# Power_Managment.net
KiCad netlist of a schematic drawn in Altium Designer
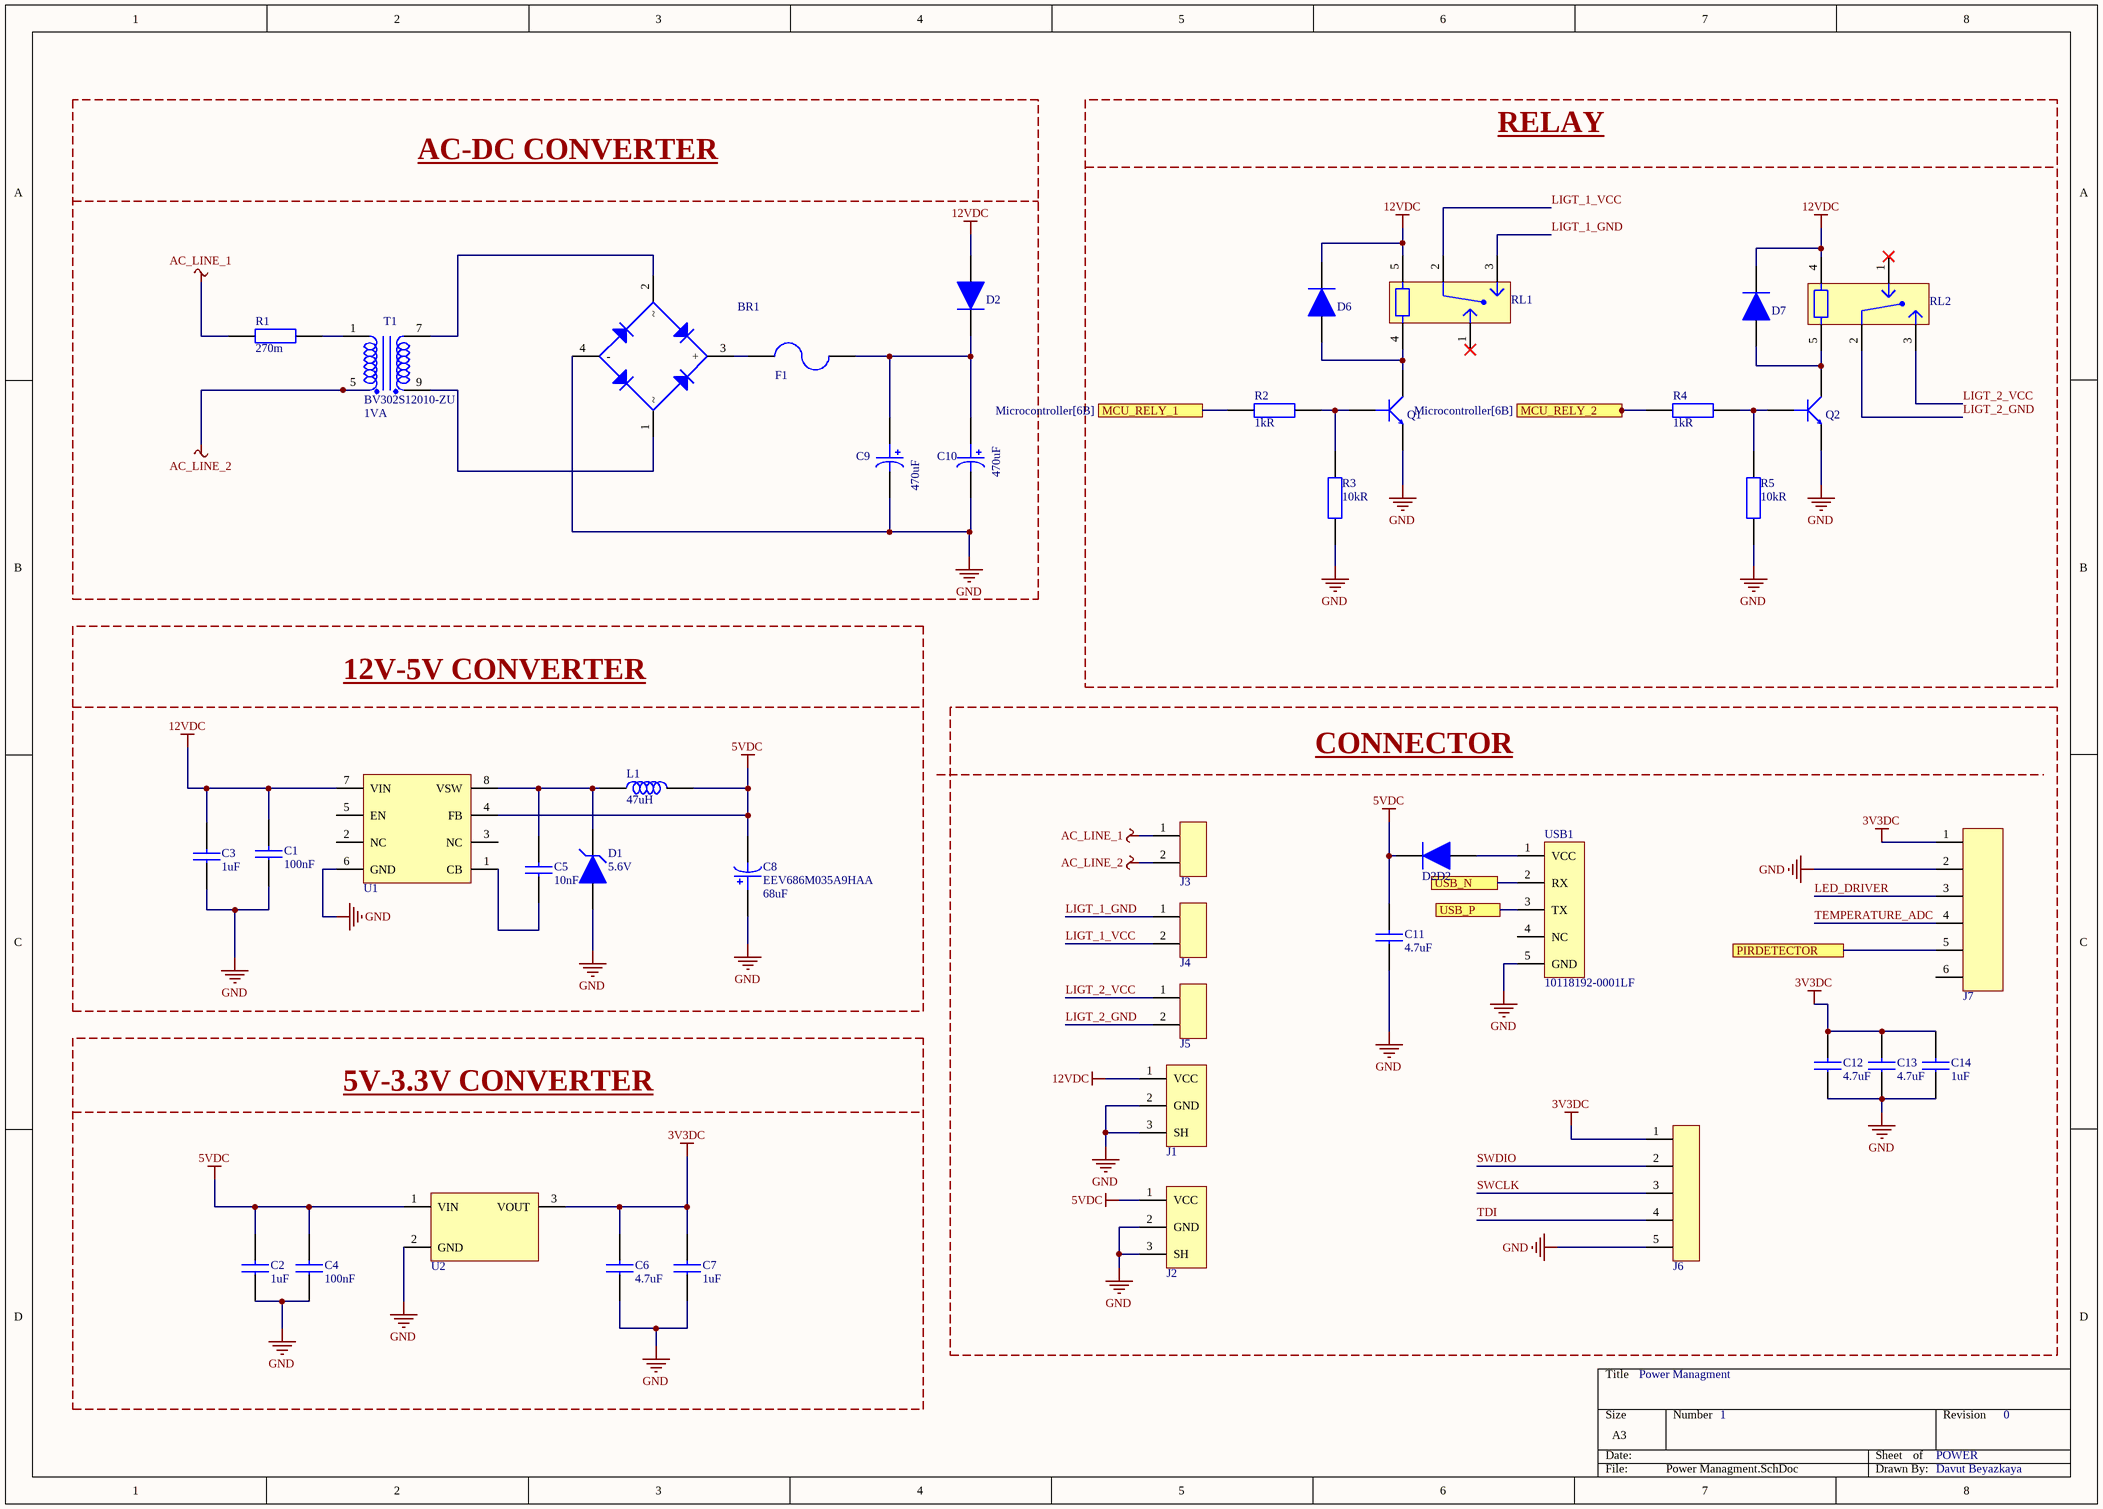
[diagram p0: Power Managment.SchDoc]

(export (version "E")
  (design (tool "Eeschema 10.0.6"))
  (components
    (comp (ref "BR1")
      (value "DB105STR")
      (footprint "DB105STR")
      (description "Bridge Diode AC-DC")
      (fields (field (name "MANUFACTURER") "Sangdest Microelectronics") (field (name "DESIGNED BY") "BERK"))
      (libsource (lib "UDEMY_Library") (part "DB105STR"))
    )
    (comp (ref "C1")
      (value "CL21B104KBCNNNC")
      (footprint "CAP_0805")
      (description "CAP CER 100nF %10 0805")
      (fields
        (field (name "MANUFACTURER") "Samsung")
        (field (name "TOLERANCE") "10%")
        (field (name "CAPACITANCE") "100nF")
        (field (name "DESIGNED BY") "BERK")
      )
      (libsource (lib "UDEMY_Library") (part "CAP CER 100nF 0805"))
    )
    (comp (ref "C2")
      (value "CL21B105KBFNNNE")
      (footprint "CAP_0805")
      (description "CAP CER 1uF %10 0805")
      (fields
        (field (name "MANUFACTURER") "Samsung")
        (field (name "TOLERANCE") "10%")
        (field (name "CAPACITANCE") "1uF")
        (field (name "DESIGNED BY") "BERK")
      )
      (libsource (lib "UDEMY_Library") (part "CAP CER 1uF 0805"))
    )
    (comp (ref "C3")
      (value "CL21B105KBFNNNE")
      (footprint "CAP_0805")
      (description "CAP CER 1uF %10 0805")
      (fields
        (field (name "MANUFACTURER") "Samsung")
        (field (name "TOLERANCE") "10%")
        (field (name "CAPACITANCE") "1uF")
        (field (name "DESIGNED BY") "BERK")
      )
      (libsource (lib "UDEMY_Library") (part "CAP CER 1uF 0805"))
    )
    (comp (ref "C4")
      (value "C0603C104K5RACTU")
      (footprint "CAP_0603")
      (description "CAP CER 100nF %10 0603 SMD")
      (fields
        (field (name "MANUFACTURER") "KEMET")
        (field (name "TOLERANCE") "10%")
        (field (name "CAPACITANCE") "100nF")
        (field (name "DESIGNED BY") "BERK")
      )
      (libsource (lib "UDEMY_Library") (part "CAP CER 100nF 0603"))
    )
    (comp (ref "C5")
      (value "0603B103K160CT")
      (footprint "CAP_0603")
      (description "CAP CER 10nF %10 0603")
      (fields
        (field (name "MANUFACTURER") "Walsin Technologies")
        (field (name "TOLERANCE") "10%")
        (field (name "CAPACITANCE") "10nF")
        (field (name "DESIGNED BY") "BERK")
      )
      (libsource (lib "UDEMY_Library") (part "CAP CER 10nF 0603"))
    )
    (comp (ref "C6")
      (value "CL21A475KAQNNNE")
      (footprint "CAP_0805")
      (description "CAP CER 4.7uF %10 0805")
      (fields
        (field (name "MANUFACTURER") "Samsung")
        (field (name "TOLERANCE") "10%")
        (field (name "CAPACITANCE") "4.7uF")
        (field (name "DESIGNED BY") "BERK")
      )
      (libsource (lib "UDEMY_Library") (part "CAP CER 4.7uF 0805"))
    )
    (comp (ref "C7")
      (value "CL21B105KBFNNNE")
      (footprint "CAP_0805")
      (description "CAP CER 1uF %10 0805")
      (fields
        (field (name "MANUFACTURER") "Samsung")
        (field (name "TOLERANCE") "10%")
        (field (name "CAPACITANCE") "1uF")
        (field (name "DESIGNED BY") "BERK")
      )
      (libsource (lib "UDEMY_Library") (part "CAP CER 1uF 0805"))
    )
    (comp (ref "C8")
      (value "EEV686M035A9HAA")
      (footprint "CAP_EEVseries")
      (description "Cap Aluminum Lytic 68uF 35V 20% (6.3 X 7.7mm) SMD 280mA 2000h 105C T/R")
      (fields
        (field (name "MANUFACTURER") "KEMET")
        (field (name "TOLERANCE") "20%")
        (field (name "CAPACITANCE") "68uF")
      )
      (libsource (lib "UDEMY_Library") (part "CAP ALU 68uF"))
    )
    (comp (ref "C9")
      (value "ESH477M050AH4AA")
      (footprint "CAP_RADIAL_D10_P5")
      (description "CAP ALU ELEC 470uF 50V RADIAL")
      (fields
        (field (name "MANUFACTURER") "KEMET")
        (field (name "TOLERANCE") "20%")
        (field (name "CAPACITANCE") "470uF")
        (field (name "DESIGNED BY") "BERK")
      )
      (libsource (lib "UDEMY_Library") (part "CAP ALU ELEC 470uF 50V"))
    )
    (comp (ref "C10")
      (value "ESH477M050AH4AA")
      (footprint "CAP_RADIAL_D10_P5")
      (description "CAP ALU ELEC 470uF 50V RADIAL")
      (fields
        (field (name "MANUFACTURER") "KEMET")
        (field (name "TOLERANCE") "20%")
        (field (name "CAPACITANCE") "470uF")
        (field (name "DESIGNED BY") "BERK")
      )
      (libsource (lib "UDEMY_Library") (part "CAP ALU ELEC 470uF 50V"))
    )
    (comp (ref "C11")
      (value "CL21A475KAQNNNE")
      (footprint "CAP_0805")
      (description "CAP CER 4.7uF %10 0805")
      (fields
        (field (name "MANUFACTURER") "Samsung")
        (field (name "TOLERANCE") "10%")
        (field (name "CAPACITANCE") "4.7uF")
        (field (name "DESIGNED BY") "BERK")
      )
      (libsource (lib "UDEMY_Library") (part "CAP CER 4.7uF 0805"))
    )
    (comp (ref "C12")
      (value "CL21A475KAQNNNE")
      (footprint "CAP_0805")
      (description "CAP CER 4.7uF %10 0805")
      (fields
        (field (name "MANUFACTURER") "Samsung")
        (field (name "TOLERANCE") "10%")
        (field (name "CAPACITANCE") "4.7uF")
        (field (name "DESIGNED BY") "BERK")
      )
      (libsource (lib "UDEMY_Library") (part "CAP CER 4.7uF 0805"))
    )
    (comp (ref "C13")
      (value "CL21A475KAQNNNE")
      (footprint "CAP_0805")
      (description "CAP CER 4.7uF %10 0805")
      (fields
        (field (name "MANUFACTURER") "Samsung")
        (field (name "TOLERANCE") "10%")
        (field (name "CAPACITANCE") "4.7uF")
        (field (name "DESIGNED BY") "BERK")
      )
      (libsource (lib "UDEMY_Library") (part "CAP CER 4.7uF 0805"))
    )
    (comp (ref "C14")
      (value "CL21B105KBFNNNE")
      (footprint "CAP_0805")
      (description "CAP CER 1uF %10 0805")
      (fields
        (field (name "MANUFACTURER") "Samsung")
        (field (name "TOLERANCE") "10%")
        (field (name "CAPACITANCE") "1uF")
        (field (name "DESIGNED BY") "BERK")
      )
      (libsource (lib "UDEMY_Library") (part "CAP CER 1uF 0805"))
    )
    (comp (ref "D1")
      (value "1SMB5919BT3G")
      (footprint "SMB")
      (description "Diode Zener Single 5.6V 5% 3W 2-Pin SMB T/R")
      (fields
        (field (name "MANUFACTURER") "ON Semiconductor")
        (field (name "TOLERANCE") "5%")
        (field (name "WORKING VOLTAGE") "5.6V")
        (field (name "DESIGNED BY") "BERK")
      )
      (libsource (lib "UDEMY_Library") (part "1SMB5919BT3G"))
    )
    (comp (ref "D2")
      (value "1N4148WS")
      (footprint "SOD323F")
      (description "Diode, Single, 75 V, 150 mA, 1 V, 4 ns")
      (fields
        (field (name "MANUFACTURER") "ON Semiconductor / Fairchild")
        (field (name "DESIGNED BY") "BERK")
      )
      (libsource (lib "UDEMY_Library") (part "1N4148WS"))
    )
    (comp (ref "D2D2")
      (value "1N4148WS")
      (footprint "SOD323F")
      (description "Diode, Single, 75 V, 150 mA, 1 V, 4 ns")
      (fields
        (field (name "MANUFACTURER") "ON Semiconductor / Fairchild")
        (field (name "DESIGNED BY") "BERK")
      )
      (libsource (lib "UDEMY_Library") (part "1N4148WS"))
    )
    (comp (ref "D6")
      (value "1N4148WS")
      (footprint "SOD323F")
      (description "Diode, Single, 75 V, 150 mA, 1 V, 4 ns")
      (fields
        (field (name "MANUFACTURER") "ON Semiconductor / Fairchild")
        (field (name "DESIGNED BY") "BERK")
      )
      (libsource (lib "UDEMY_Library") (part "1N4148WS"))
    )
    (comp (ref "D7")
      (value "1N4148WS")
      (footprint "SOD323F")
      (description "Diode, Single, 75 V, 150 mA, 1 V, 4 ns")
      (fields
        (field (name "MANUFACTURER") "ON Semiconductor / Fairchild")
        (field (name "DESIGNED BY") "BERK")
      )
      (libsource (lib "UDEMY_Library") (part "1N4148WS"))
    )
    (comp (ref "F1")
      (value "3413.0216.22")
      (footprint "3413.0216.22")
      (description "FUSE BRD MNT 1A 32VAC 63VDC 1206")
      (fields (field (name "MANUFACTURER") "Schurter") (field (name "DESIGNED BY") "BERK"))
      (libsource (lib "UDEMY_Library") (part "FUSE 3413.0216.22"))
    )
    (comp (ref "J1")
      (value "PJ-037AH-SMT-TR")
      (footprint "JACK")
      (description "DC Power Connectors Power Jacks")
      (fields (field (name "MANUFACTURER") "CUI") (field (name "DESIGNED BY") "BERK"))
      (libsource (lib "UDEMY_Library") (part "PJ-037AH-SMT-TR"))
    )
    (comp (ref "J2")
      (value "PJ-037AH-SMT-TR")
      (footprint "JACK")
      (description "DC Power Connectors Power Jacks")
      (fields (field (name "MANUFACTURER") "CUI") (field (name "DESIGNED BY") "BERK"))
      (libsource (lib "UDEMY_Library") (part "PJ-037AH-SMT-TR"))
    )
    (comp (ref "J3")
      (value "TBP01R1-508-02BE")
      (footprint "TBP01R1-508")
      (description "Conn Shrouded Header HDR 2 POS 5.08mm Solder RA Side Entry Thru-Hole Bag")
      (fields (field (name "MANUFACTURER") "CUI") (field (name "DESIGNED BY") "BERK"))
      (libsource (lib "UDEMY_Library") (part "TBP01R1-508-02BE"))
    )
    (comp (ref "J4")
      (value "TBP01R1-508-02BE")
      (footprint "TBP01R1-508")
      (description "Conn Shrouded Header HDR 2 POS 5.08mm Solder RA Side Entry Thru-Hole Bag")
      (fields (field (name "MANUFACTURER") "CUI") (field (name "DESIGNED BY") "BERK"))
      (libsource (lib "UDEMY_Library") (part "TBP01R1-508-02BE"))
    )
    (comp (ref "J5")
      (value "TBP01R1-508-02BE")
      (footprint "TBP01R1-508")
      (description "Conn Shrouded Header HDR 2 POS 5.08mm Solder RA Side Entry Thru-Hole Bag")
      (fields (field (name "MANUFACTURER") "CUI") (field (name "DESIGNED BY") "BERK"))
      (libsource (lib "UDEMY_Library") (part "TBP01R1-508-02BE"))
    )
    (comp (ref "J6")
      (value "SMH-105-02-L-S")
      (footprint "PINHEADER1X5_RA")
      (description ".100 C.L. HORIZONTAL SMT SOCKET")
      (fields (field (name "MANUFACTURER") "Samtec") (field (name "DESIGNED BY") "BERK"))
      (libsource (lib "UDEMY_Library") (part "SMH-105-02-L-S"))
    )
    (comp (ref "J7")
      (value "64800611622")
      (footprint "64800611622")
      (description "1.50mm 6PIN Connector")
      (fields (field (name "MANUFACTURER") "Wurth Electronics"))
      (libsource (lib "UDEMY_Library") (part "64800611622_conn_6pin"))
    )
    (comp (ref "L1")
      (value "78438335470")
      (footprint "IND_1212")
      (description "FIXED IND 47UH 390MA 2.3 OHM SMD")
      (fields
        (field (name "MANUFACTURER") "Wurth Electronics")
        (field (name "TOLERANCE") "30%")
        (field (name "INDUCTANCE") "47uH")
        (field (name "DESIGNED BY") "BERK")
      )
      (libsource (lib "UDEMY_Library") (part "IND 47uH"))
    )
    (comp (ref "Q1")
      (value "MMBT3904-7-F")
      (footprint "SOT-23F")
      (description "Transistor General Purpose BJT NPN 40 Volt 0.2A Automotive 3-Pin SOT-23")
      (fields (field (name "MANUFACTURER") "Diodes Zetex") (field (name "DESIGNED BY") "BERK"))
      (libsource (lib "UDEMY_Library") (part "MMBT3904-7-F"))
    )
    (comp (ref "Q2")
      (value "MMBT3904-7-F")
      (footprint "SOT-23F")
      (description "Transistor General Purpose BJT NPN 40 Volt 0.2A Automotive 3-Pin SOT-23")
      (fields (field (name "MANUFACTURER") "Diodes Zetex") (field (name "DESIGNED BY") "BERK"))
      (libsource (lib "UDEMY_Library") (part "MMBT3904-7-F"))
    )
    (comp (ref "R1")
      (value "5WD27")
      (footprint "RES_AXIAL_W")
      (description "Resistor 5 Watt Cermet Wirewound Flameproof .27 Ohm 5% Axial Lead")
      (fields
        (field (name "MANUFACTURER") "NTE Electronics")
        (field (name "TOLERANCE") "5%")
        (field (name "RESISTANCE") "270m")
        (field (name "DESIGNED BY") "BERK")
      )
      (libsource (lib "UDEMY_Library") (part "5WD27"))
    )
    (comp (ref "R2")
      (value "RC0603FR-0710KL")
      (footprint "RES_0603")
      (description "RES 1K %1 OHM 0603 SMD")
      (fields
        (field (name "MANUFACTURER") "Yageo")
        (field (name "MANUFACTURER PART NUMBER") "RC0603JR-071KL")
        (field (name "RESISTANCE") "1kR")
        (field (name "DESIGNED BY") "BERK")
      )
      (libsource (lib "UDEMY_Library") (part "RES 1K OHM 0603"))
    )
    (comp (ref "R3")
      (value "RC0603FR-0710KL")
      (footprint "RES_0603")
      (description "RES 10K %1 OHM 0603 SMD")
      (fields
        (field (name "MANUFACTURER") "Yageo")
        (field (name "TOLERANCE") "1%")
        (field (name "RESISTANCE") "10kR")
        (field (name "DESIGNED BY") "BERK")
      )
      (libsource (lib "UDEMY_Library") (part "RES 10K OHM 0603"))
    )
    (comp (ref "R4")
      (value "RC0603FR-0710KL")
      (footprint "RES_0603")
      (description "RES 1K %1 OHM 0603 SMD")
      (fields
        (field (name "MANUFACTURER") "Yageo")
        (field (name "MANUFACTURER PART NUMBER") "RC0603JR-071KL")
        (field (name "RESISTANCE") "1kR")
        (field (name "DESIGNED BY") "BERK")
      )
      (libsource (lib "UDEMY_Library") (part "RES 1K OHM 0603"))
    )
    (comp (ref "R5")
      (value "RC0603FR-0710KL")
      (footprint "RES_0603")
      (description "RES 10K %1 OHM 0603 SMD")
      (fields
        (field (name "MANUFACTURER") "Yageo")
        (field (name "TOLERANCE") "1%")
        (field (name "RESISTANCE") "10kR")
        (field (name "DESIGNED BY") "BERK")
      )
      (libsource (lib "UDEMY_Library") (part "RES 10K OHM 0603"))
    )
    (comp (ref "RL1")
      (value "ALQ112")
      (footprint "ALQ112")
      (description "General Purpose Relay SPDT (1 Form C) 12VDC Coil Through Hole")
      (fields (field (name "MANUFACTURER") "Panasonic") (field (name "DESIGNED BY") "BERK"))
      (libsource (lib "UDEMY_Library") (part "ALQ112"))
    )
    (comp (ref "RL2")
      (value "ALQ112")
      (footprint "ALQ112")
      (description "General Purpose Relay SPDT (1 Form C) 12VDC Coil Through Hole")
      (fields (field (name "MANUFACTURER") "Panasonic") (field (name "DESIGNED BY") "BERK"))
      (libsource (lib "") (part "ALQ112_1"))
    )
    (comp (ref "T1")
      (value "BV302S12010-ZU")
      (footprint "BV302S")
      (description "230-12 Transformer 1VA")
      (fields
        (field (name "MANUFACTURER") "Zettler Magnetics")
        (field (name "RATED POWER") "1VA")
        (field (name "DESIGNED BY") "BERK")
      )
      (libsource (lib "UDEMY_Library") (part "BV302S12010-ZU"))
    )
    (comp (ref "U1")
      (value "LM2675MX-12/NOPB")
      (footprint "SOIC8")
      (description "Switching Voltage Regulators Pwr Cnvtr Hi Eff 1A SD Vtg Reg")
      (fields (field (name "MANUFACTURER") "TI National Semiconductor") (field (name "DESIGNED BY") "BERK"))
      (libsource (lib "UDEMY_Library") (part "LM2675MX-12/NOPB"))
    )
    (comp (ref "U2")
      (value "AP7361-33E-13")
      (footprint "SOT223")
      (description "LDO Regulator Pos 3.3V 1A 4-Pin(3+Tab) SOT-223 T/R")
      (fields (field (name "MANUFACTURER") "Diodes") (field (name "DESIGNED BY") "BERK"))
      (libsource (lib "UDEMY_Library") (part "AP7361-33E-13"))
    )
    (comp (ref "USB1")
      (value "10118192-0001LF")
      (footprint "MICRO_B_USB")
      (description "CONN RCPT USB2.0 MICRO B SMD R/A")
      (fields (field (name "MANUFACTURER") "Amphenol FCI") (field (name "DESIGNED BY") "BERK"))
      (libsource (lib "UDEMY_Library") (part "Micro B USB Connector"))
    )
  )
  (nets
    (net (code "1") (name "/LED_DRIVER") (class "Default") (node (ref "J7") (pin "3") (pintype "power_in")))
    (net (code "2") (name "/LIGT_1_GND") (class "Default")
      (node (ref "J4") (pin "1") (pinfunction "1_1") (pintype "power_in"))
      (node (ref "RL1") (pin "3") (pinfunction "3_3") (pintype "passive"))
    )
    (net (code "3") (name "/LIGT_1_VCC") (class "Default")
      (node (ref "J4") (pin "2") (pinfunction "2_2") (pintype "power_in"))
      (node (ref "RL1") (pin "2") (pinfunction "2_2") (pintype "passive"))
    )
    (net (code "4") (name "/LIGT_2_GND") (class "Default")
      (node (ref "J5") (pin "2") (pinfunction "2_2") (pintype "power_in"))
      (node (ref "RL2") (pin "2") (pinfunction "2_2") (pintype "passive"))
    )
    (net (code "5") (name "/LIGT_2_VCC") (class "Default")
      (node (ref "J5") (pin "1") (pinfunction "1_1") (pintype "power_in"))
      (node (ref "RL2") (pin "3") (pinfunction "3_3") (pintype "passive"))
    )
    (net (code "6") (name "/MCU_RELY_1") (class "Default")
      (node (ref "R2") (pin "1") (pinfunction "1_1") (pintype "passive"))
    )
    (net (code "7") (name "/MCU_RELY_2") (class "Default")
      (node (ref "R4") (pin "1") (pinfunction "1_1") (pintype "passive"))
    )
    (net (code "8") (name "/PIRDETECTOR") (class "Default") (node (ref "J7") (pin "5") (pintype "power_in")))
    (net (code "9") (name "/SWCLK") (class "Default")
      (node (ref "J6") (pin "3") (pinfunction "3_3") (pintype "power_in"))
    )
    (net (code "10") (name "/SWDIO") (class "Default")
      (node (ref "J6") (pin "2") (pinfunction "2_2") (pintype "power_in"))
    )
    (net (code "11") (name "/TDI") (class "Default")
      (node (ref "J6") (pin "4") (pinfunction "4_4") (pintype "power_in"))
    )
    (net (code "12") (name "/TEMPERATURE_ADC") (class "Default")
      (node (ref "J7") (pin "4") (pintype "power_in"))
    )
    (net (code "13") (name "/USB_N") (class "Default")
      (node (ref "USB1") (pin "2") (pinfunction "RX_2") (pintype "power_in"))
    )
    (net (code "14") (name "/USB_P") (class "Default")
      (node (ref "USB1") (pin "3") (pinfunction "TX_3") (pintype "power_in"))
    )
    (net (code "15") (name "3V3DC") (class "Default")
      (node (ref "C12") (pin "2") (pinfunction "2_2") (pintype "passive"))
      (node (ref "C13") (pin "2") (pinfunction "2_2") (pintype "passive"))
      (node (ref "C14") (pin "2") (pinfunction "2_2") (pintype "passive"))
      (node (ref "C6") (pin "2") (pinfunction "2_2") (pintype "passive"))
      (node (ref "C7") (pin "2") (pinfunction "2_2") (pintype "passive"))
      (node (ref "J6") (pin "1") (pinfunction "1_1") (pintype "power_in"))
      (node (ref "J7") (pin "1") (pintype "power_in"))
      (node (ref "U2") (pin "3") (pinfunction "VOUT_3") (pintype "passive"))
    )
    (net (code "16") (name "5VDC") (class "Default")
      (node (ref "C11") (pin "2") (pinfunction "2_2") (pintype "passive"))
      (node (ref "C2") (pin "2") (pinfunction "2_2") (pintype "passive"))
      (node (ref "C4") (pin "2") (pinfunction "2_2") (pintype "passive"))
      (node (ref "C8") (pin "2") (pinfunction "2_2") (pintype "passive"))
      (node (ref "D2D2") (pin "1") (pinfunction "1_1") (pintype "power_in"))
      (node (ref "J2") (pin "1") (pinfunction "VCC_1") (pintype "power_in"))
      (node (ref "L1") (pin "2") (pinfunction "2_2") (pintype "passive"))
      (node (ref "U1") (pin "4") (pinfunction "FB_4") (pintype "passive"))
      (node (ref "U2") (pin "1") (pinfunction "VIN_1") (pintype "passive"))
    )
    (net (code "17") (name "12VDC") (class "Default")
      (node (ref "C1") (pin "2") (pinfunction "2_2") (pintype "passive"))
      (node (ref "C3") (pin "2") (pinfunction "2_2") (pintype "passive"))
      (node (ref "D2") (pin "2") (pinfunction "2_2") (pintype "power_in"))
      (node (ref "D6") (pin "1") (pinfunction "1_1") (pintype "power_in"))
      (node (ref "D7") (pin "1") (pinfunction "1_1") (pintype "power_in"))
      (node (ref "J1") (pin "1") (pinfunction "VCC_1") (pintype "power_in"))
      (node (ref "RL1") (pin "5") (pinfunction "5_5") (pintype "passive"))
      (node (ref "RL2") (pin "4") (pinfunction "4_4") (pintype "passive"))
      (node (ref "U1") (pin "7") (pinfunction "VIN_7") (pintype "passive"))
    )
    (net (code "18") (name "AC_LINE_1") (class "Default")
      (node (ref "J3") (pin "1") (pinfunction "1_1") (pintype "power_in"))
      (node (ref "R1") (pin "1") (pinfunction "1_1") (pintype "passive"))
    )
    (net (code "19") (name "AC_LINE_2") (class "Default")
      (node (ref "J3") (pin "2") (pinfunction "2_2") (pintype "power_in"))
      (node (ref "T1") (pin "5") (pinfunction "5_5") (pintype "passive"))
    )
    (net (code "20") (name "GND") (class "Default")
      (node (ref "BR1") (pin "4") (pinfunction "-_4") (pintype "passive"))
      (node (ref "C1") (pin "1") (pinfunction "1_1") (pintype "passive"))
      (node (ref "C10") (pin "2") (pinfunction "2_2") (pintype "passive"))
      (node (ref "C11") (pin "1") (pinfunction "1_1") (pintype "passive"))
      (node (ref "C12") (pin "1") (pinfunction "1_1") (pintype "passive"))
      (node (ref "C13") (pin "1") (pinfunction "1_1") (pintype "passive"))
      (node (ref "C14") (pin "1") (pinfunction "1_1") (pintype "passive"))
      (node (ref "C2") (pin "1") (pinfunction "1_1") (pintype "passive"))
      (node (ref "C3") (pin "1") (pinfunction "1_1") (pintype "passive"))
      (node (ref "C4") (pin "1") (pinfunction "1_1") (pintype "passive"))
      (node (ref "C6") (pin "1") (pinfunction "1_1") (pintype "passive"))
      (node (ref "C7") (pin "1") (pinfunction "1_1") (pintype "passive"))
      (node (ref "C8") (pin "1") (pinfunction "1_1") (pintype "passive"))
      (node (ref "C9") (pin "2") (pinfunction "2_2") (pintype "passive"))
      (node (ref "D1") (pin "A") (pinfunction "A_A") (pintype "passive"))
      (node (ref "J1") (pin "2") (pinfunction "GND_2") (pintype "power_in"))
      (node (ref "J1") (pin "3") (pinfunction "SH_3") (pintype "power_in"))
      (node (ref "J2") (pin "2") (pinfunction "GND_2") (pintype "power_in"))
      (node (ref "J2") (pin "3") (pinfunction "SH_3") (pintype "power_in"))
      (node (ref "J6") (pin "5") (pinfunction "5_5") (pintype "power_in"))
      (node (ref "J7") (pin "2") (pintype "power_in"))
      (node (ref "Q1") (pin "2") (pinfunction "E_2") (pintype "power_in"))
      (node (ref "Q2") (pin "2") (pinfunction "E_2") (pintype "power_in"))
      (node (ref "R3") (pin "1") (pinfunction "1_1") (pintype "passive"))
      (node (ref "R5") (pin "1") (pinfunction "1_1") (pintype "passive"))
      (node (ref "U1") (pin "6") (pinfunction "GND_6") (pintype "passive"))
      (node (ref "U2") (pin "2") (pinfunction "GND_2") (pintype "passive"))
      (node (ref "USB1") (pin "5") (pinfunction "GND_5") (pintype "power_in"))
    )
    (net (code "21") (name "Net-(BR1-+)") (class "Default")
      (node (ref "BR1") (pin "3") (pinfunction "+_3") (pintype "passive"))
      (node (ref "F1") (pin "1") (pinfunction "1_1") (pintype "passive"))
    )
    (net (code "22") (name "Net-(BR1-~-Pad1)") (class "Default")
      (node (ref "BR1") (pin "1") (pinfunction "~_1") (pintype "passive"))
      (node (ref "T1") (pin "9") (pinfunction "9_9") (pintype "passive"))
    )
    (net (code "23") (name "Net-(BR1-~-Pad2)") (class "Default")
      (node (ref "BR1") (pin "2") (pinfunction "~_2") (pintype "passive"))
      (node (ref "T1") (pin "7") (pinfunction "7_7") (pintype "passive"))
    )
    (net (code "24") (name "Net-(C10-Pad1)") (class "Default")
      (node (ref "C10") (pin "1") (pinfunction "1_1") (pintype "passive"))
      (node (ref "C9") (pin "1") (pinfunction "1_1") (pintype "passive"))
      (node (ref "D2") (pin "1") (pinfunction "1_1") (pintype "power_in"))
      (node (ref "F1") (pin "2") (pinfunction "2_2") (pintype "passive"))
    )
    (net (code "25") (name "Net-(Q1-B)") (class "Default")
      (node (ref "Q1") (pin "1") (pinfunction "B_1") (pintype "power_in"))
      (node (ref "R2") (pin "2") (pinfunction "2_2") (pintype "passive"))
      (node (ref "R3") (pin "2") (pinfunction "2_2") (pintype "passive"))
    )
    (net (code "26") (name "Net-(Q1-C)") (class "Default")
      (node (ref "D6") (pin "2") (pinfunction "2_2") (pintype "power_in"))
      (node (ref "Q1") (pin "3") (pinfunction "C_3") (pintype "power_in"))
      (node (ref "RL1") (pin "4") (pinfunction "4_4") (pintype "passive"))
    )
    (net (code "27") (name "Net-(Q2-B)") (class "Default")
      (node (ref "Q2") (pin "1") (pinfunction "B_1") (pintype "power_in"))
      (node (ref "R4") (pin "2") (pinfunction "2_2") (pintype "passive"))
      (node (ref "R5") (pin "2") (pinfunction "2_2") (pintype "passive"))
    )
    (net (code "28") (name "Net-(Q2-C)") (class "Default")
      (node (ref "D7") (pin "2") (pinfunction "2_2") (pintype "power_in"))
      (node (ref "Q2") (pin "3") (pinfunction "C_3") (pintype "power_in"))
      (node (ref "RL2") (pin "5") (pinfunction "5_5") (pintype "passive"))
    )
    (net (code "29") (name "Net-(R1-Pad2)") (class "Default")
      (node (ref "R1") (pin "2") (pinfunction "2_2") (pintype "passive"))
      (node (ref "T1") (pin "1") (pinfunction "1_1") (pintype "passive"))
    )
    (net (code "30") (name "Net-(U1-CB)") (class "Default")
      (node (ref "C5") (pin "1") (pinfunction "1_1") (pintype "passive"))
      (node (ref "U1") (pin "1") (pinfunction "CB_1") (pintype "passive"))
    )
    (net (code "31") (name "Net-(U1-VSW)") (class "Default")
      (node (ref "C5") (pin "2") (pinfunction "2_2") (pintype "passive"))
      (node (ref "D1") (pin "C") (pinfunction "C_C") (pintype "passive"))
      (node (ref "L1") (pin "1") (pinfunction "1_1") (pintype "passive"))
      (node (ref "U1") (pin "8") (pinfunction "VSW_8") (pintype "passive"))
    )
    (net (code "32") (name "Net-(USB1-VCC)") (class "Default")
      (node (ref "D2D2") (pin "2") (pinfunction "2_2") (pintype "power_in"))
      (node (ref "USB1") (pin "1") (pinfunction "VCC_1") (pintype "power_in"))
    )
    (net (code "33") (name "unconnected-(J7-Pad6)") (class "Default")
      (node (ref "J7") (pin "6") (pintype "power_in"))
    )
    (net (code "34") (name "unconnected-(RL1-Pad1)") (class "Default")
      (node (ref "RL1") (pin "1") (pinfunction "1_1") (pintype "passive+no_connect"))
    )
    (net (code "35") (name "unconnected-(RL2-Pad1)") (class "Default")
      (node (ref "RL2") (pin "1") (pinfunction "1_1") (pintype "passive+no_connect"))
    )
    (net (code "36") (name "unconnected-(U1-EN-Pad5)") (class "Default")
      (node (ref "U1") (pin "5") (pinfunction "EN_5") (pintype "passive"))
    )
    (net (code "37") (name "unconnected-(U1-NC-Pad2)") (class "Default")
      (node (ref "U1") (pin "2") (pinfunction "NC_2") (pintype "passive"))
    )
    (net (code "38") (name "unconnected-(U1-NC-Pad3)") (class "Default")
      (node (ref "U1") (pin "3") (pinfunction "NC_3") (pintype "passive"))
    )
    (net (code "39") (name "unconnected-(USB1-NC-Pad4)") (class "Default")
      (node (ref "USB1") (pin "4") (pinfunction "NC_4") (pintype "power_in"))
    )
  )
)
